# Bioreactor_Motor_PCB.net
KiCad netlist of a schematic drawn in EAGLE
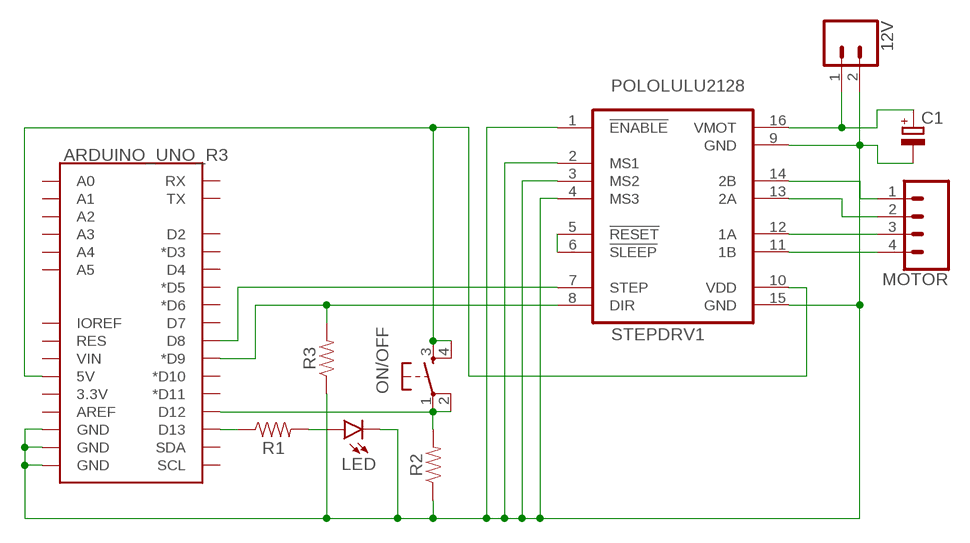
[diagram p0: schematic, sheet 1]

(export (version "E")
  (design (tool "Eeschema 10.0.6"))
  (components
    (comp (ref "12V")
      (value "CONN_02POLAR")
      (footprint "eagle-import:MOLEX-1X2")
      (libsource (lib "eagle-import") (part "CONN_02POLAR"))
    )
    (comp (ref "ARDUINO_UNO_R3")
      (value "ARDUINO_UNO_R3_SHIELDBASIC")
      (footprint "eagle-import:UNO_R3_SHIELD")
      (libsource (lib "eagle-import") (part "ARDUINO_UNO_R3_SHIELDBASIC"))
    )
    (comp (ref "C1")
      (value "CPOL-EUE3.5-8")
      (footprint "eagle-import:E3,5-8")
      (libsource (lib "eagle-import") (part "CPOL-EUE3.5-8"))
    )
    (comp (ref "LED")
      (value "TLLG4400")
      (footprint "eagle-import:LED3MM")
      (fields (field (name "MF") "VISHAY SEMICONDUCTOR"))
      (libsource (lib "eagle-import") (part "TLLG4400"))
    )
    (comp (ref "MOTOR")
      (value "CONN_04POLAR")
      (footprint "eagle-import:MOLEX-1X4")
      (libsource (lib "eagle-import") (part "CONN_04POLAR"))
    )
    (comp (ref "ON/OFF")
      (value "TAC_SWITCHPTH")
      (footprint "eagle-import:TACTILE-PTH")
      (libsource (lib "eagle-import") (part "TAC_SWITCHPTH"))
    )
    (comp (ref "R1")
      (value "1M")
      (footprint "eagle-import:AXIAL-0.3")
      (libsource (lib "eagle-import") (part "1MOHM-HORIZ-1/4W-5%"))
    )
    (comp (ref "R2")
      (value "1k")
      (footprint "eagle-import:AXIAL-0.3")
      (libsource (lib "eagle-import") (part "1KOHM-HORIZ-1/4W-1%"))
    )
    (comp (ref "R3")
      (value "1k")
      (footprint "eagle-import:AXIAL-0.3")
      (libsource (lib "eagle-import") (part "1KOHM-HORIZ-1/4W-1%"))
    )
    (comp (ref "STEPDRV1")
      (value "POLOLULU2128")
      (footprint "eagle-import:POLOLULU2128")
      (libsource (lib "eagle-import") (part "POLOLULU2128"))
    )
  )
  (nets
    (net (code "1") (name "Net-(ARDUINO_UNO_R3-*D9)") (class "Default")
      (node (ref "ARDUINO_UNO_R3") (pin "D9") (pinfunction "*D9_D9") (pintype "bidirectional"))
      (node (ref "R3") (pin "P$2") (pinfunction "2_P$2") (pintype "passive"))
      (node (ref "STEPDRV1") (pin "8") (pinfunction "DIR_8") (pintype "input"))
    )
    (net (code "2") (name "Net-(LED-C)") (class "Default")
      (node (ref "12V") (pin "2") (pinfunction "2_2") (pintype "passive"))
      (node (ref "ARDUINO_UNO_R3") (pin "GND@0") (pinfunction "GND_GND@0") (pintype "bidirectional"))
      (node (ref "ARDUINO_UNO_R3") (pin "GND@1") (pinfunction "GND_GND@1") (pintype "bidirectional"))
      (node (ref "ARDUINO_UNO_R3") (pin "GND@2") (pinfunction "GND_GND@2") (pintype "bidirectional"))
      (node (ref "C1") (pin "-") (pinfunction "-_-") (pintype "passive"))
      (node (ref "LED") (pin "K") (pinfunction "C_K") (pintype "passive"))
      (node (ref "R2") (pin "P$1") (pinfunction "1_P$1") (pintype "passive"))
      (node (ref "R3") (pin "P$1") (pinfunction "1_P$1") (pintype "passive"))
      (node (ref "STEPDRV1") (pin "1") (pinfunction "~{ENABLE}_1") (pintype "input"))
      (node (ref "STEPDRV1") (pin "15") (pinfunction "GND_15") (pintype "power_in"))
      (node (ref "STEPDRV1") (pin "2") (pinfunction "MS1_2") (pintype "input"))
      (node (ref "STEPDRV1") (pin "3") (pinfunction "MS2_3") (pintype "input"))
      (node (ref "STEPDRV1") (pin "4") (pinfunction "MS3_4") (pintype "input"))
      (node (ref "STEPDRV1") (pin "9") (pinfunction "GND_9") (pintype "power_in"))
    )
    (net (code "3") (name "Net-(R1-1)") (class "Default")
      (node (ref "ARDUINO_UNO_R3") (pin "D13") (pinfunction "D13_D13") (pintype "bidirectional"))
      (node (ref "R1") (pin "P$1") (pinfunction "1_P$1") (pintype "passive"))
    )
    (net (code "4") (name "Net-(R1-2)") (class "Default")
      (node (ref "LED") (pin "A") (pinfunction "A_A") (pintype "passive"))
      (node (ref "R1") (pin "P$2") (pinfunction "2_P$2") (pintype "passive"))
    )
    (net (code "5") (name "Net-(R2-2)") (class "Default")
      (node (ref "ARDUINO_UNO_R3") (pin "D12") (pinfunction "D12_D12") (pintype "bidirectional"))
      (node (ref "ON/OFF") (pin "1") (pinfunction "1_1") (pintype "passive"))
      (node (ref "ON/OFF") (pin "2") (pinfunction "2_2") (pintype "passive"))
      (node (ref "R2") (pin "P$2") (pinfunction "2_P$2") (pintype "passive"))
    )
    (net (code "6") (name "Net-(STEPDRV1-1A)") (class "Default")
      (node (ref "MOTOR") (pin "3") (pinfunction "3_3") (pintype "passive"))
      (node (ref "STEPDRV1") (pin "12") (pinfunction "1A_12") (pintype "output"))
    )
    (net (code "7") (name "Net-(STEPDRV1-1B)") (class "Default")
      (node (ref "MOTOR") (pin "4") (pinfunction "4_4") (pintype "passive"))
      (node (ref "STEPDRV1") (pin "11") (pinfunction "1B_11") (pintype "output"))
    )
    (net (code "8") (name "Net-(STEPDRV1-2A)") (class "Default")
      (node (ref "MOTOR") (pin "2") (pinfunction "2_2") (pintype "passive"))
      (node (ref "STEPDRV1") (pin "13") (pinfunction "2A_13") (pintype "output"))
    )
    (net (code "9") (name "Net-(STEPDRV1-2B)") (class "Default")
      (node (ref "MOTOR") (pin "1") (pinfunction "1_1") (pintype "passive"))
      (node (ref "STEPDRV1") (pin "14") (pinfunction "2B_14") (pintype "output"))
    )
    (net (code "10") (name "Net-(STEPDRV1-STEP)") (class "Default")
      (node (ref "ARDUINO_UNO_R3") (pin "D8") (pinfunction "D8_D8") (pintype "bidirectional"))
      (node (ref "STEPDRV1") (pin "7") (pinfunction "STEP_7") (pintype "input"))
    )
    (net (code "11") (name "Net-(STEPDRV1-VDD)") (class "Default")
      (node (ref "ARDUINO_UNO_R3") (pin "5V") (pinfunction "5V_5V") (pintype "bidirectional"))
      (node (ref "ON/OFF") (pin "3") (pinfunction "3_3") (pintype "passive"))
      (node (ref "ON/OFF") (pin "4") (pinfunction "4_4") (pintype "passive"))
      (node (ref "STEPDRV1") (pin "10") (pinfunction "VDD_10") (pintype "power_in"))
    )
    (net (code "12") (name "Net-(STEPDRV1-VMOT)") (class "Default")
      (node (ref "12V") (pin "1") (pinfunction "1_1") (pintype "passive"))
      (node (ref "C1") (pin "+") (pinfunction "+_+") (pintype "passive"))
      (node (ref "STEPDRV1") (pin "16") (pinfunction "VMOT_16") (pintype "power_in"))
    )
    (net (code "13") (name "Net-(STEPDRV1-~{RESET})") (class "Default")
      (node (ref "STEPDRV1") (pin "5") (pinfunction "~{RESET}_5") (pintype "input"))
      (node (ref "STEPDRV1") (pin "6") (pinfunction "~{SLEEP}_6") (pintype "input"))
    )
    (net (code "14") (name "unconnected-(ARDUINO_UNO_R3-*D3-PadD3)") (class "Default")
      (node (ref "ARDUINO_UNO_R3") (pin "D3") (pinfunction "*D3_D3") (pintype "bidirectional"))
    )
    (net (code "15") (name "unconnected-(ARDUINO_UNO_R3-*D5-PadD5)") (class "Default")
      (node (ref "ARDUINO_UNO_R3") (pin "D5") (pinfunction "*D5_D5") (pintype "bidirectional"))
    )
    (net (code "16") (name "unconnected-(ARDUINO_UNO_R3-*D6-PadD6)") (class "Default")
      (node (ref "ARDUINO_UNO_R3") (pin "D6") (pinfunction "*D6_D6") (pintype "bidirectional"))
    )
    (net (code "17") (name "unconnected-(ARDUINO_UNO_R3-*D10-PadD10)") (class "Default")
      (node (ref "ARDUINO_UNO_R3") (pin "D10") (pinfunction "*D10_D10") (pintype "bidirectional"))
    )
    (net (code "18") (name "unconnected-(ARDUINO_UNO_R3-*D11-PadD11)") (class "Default")
      (node (ref "ARDUINO_UNO_R3") (pin "D11") (pinfunction "*D11_D11") (pintype "bidirectional"))
    )
    (net (code "19") (name "unconnected-(ARDUINO_UNO_R3-Pad3.3V)") (class "Default")
      (node (ref "ARDUINO_UNO_R3") (pin "3.3V") (pinfunction "3.3V_3.3V") (pintype "bidirectional"))
    )
    (net (code "20") (name "unconnected-(ARDUINO_UNO_R3-PadA0)") (class "Default")
      (node (ref "ARDUINO_UNO_R3") (pin "A0") (pinfunction "A0_A0") (pintype "bidirectional"))
    )
    (net (code "21") (name "unconnected-(ARDUINO_UNO_R3-PadA1)") (class "Default")
      (node (ref "ARDUINO_UNO_R3") (pin "A1") (pinfunction "A1_A1") (pintype "bidirectional"))
    )
    (net (code "22") (name "unconnected-(ARDUINO_UNO_R3-PadA2)") (class "Default")
      (node (ref "ARDUINO_UNO_R3") (pin "A2") (pinfunction "A2_A2") (pintype "bidirectional"))
    )
    (net (code "23") (name "unconnected-(ARDUINO_UNO_R3-PadA3)") (class "Default")
      (node (ref "ARDUINO_UNO_R3") (pin "A3") (pinfunction "A3_A3") (pintype "bidirectional"))
    )
    (net (code "24") (name "unconnected-(ARDUINO_UNO_R3-PadA4)") (class "Default")
      (node (ref "ARDUINO_UNO_R3") (pin "A4") (pinfunction "A4_A4") (pintype "bidirectional"))
    )
    (net (code "25") (name "unconnected-(ARDUINO_UNO_R3-PadA5)") (class "Default")
      (node (ref "ARDUINO_UNO_R3") (pin "A5") (pinfunction "A5_A5") (pintype "bidirectional"))
    )
    (net (code "26") (name "unconnected-(ARDUINO_UNO_R3-PadAREF)") (class "Default")
      (node (ref "ARDUINO_UNO_R3") (pin "AREF") (pinfunction "AREF_AREF") (pintype "bidirectional"))
    )
    (net (code "27") (name "unconnected-(ARDUINO_UNO_R3-PadD2)") (class "Default")
      (node (ref "ARDUINO_UNO_R3") (pin "D2") (pinfunction "D2_D2") (pintype "bidirectional"))
    )
    (net (code "28") (name "unconnected-(ARDUINO_UNO_R3-PadD4)") (class "Default")
      (node (ref "ARDUINO_UNO_R3") (pin "D4") (pinfunction "D4_D4") (pintype "bidirectional"))
    )
    (net (code "29") (name "unconnected-(ARDUINO_UNO_R3-PadD7)") (class "Default")
      (node (ref "ARDUINO_UNO_R3") (pin "D7") (pinfunction "D7_D7") (pintype "bidirectional"))
    )
    (net (code "30") (name "unconnected-(ARDUINO_UNO_R3-PadIOREF)") (class "Default")
      (node (ref "ARDUINO_UNO_R3") (pin "IOREF") (pinfunction "IOREF_IOREF") (pintype "bidirectional"))
    )
    (net (code "31") (name "unconnected-(ARDUINO_UNO_R3-PadRES)") (class "Default")
      (node (ref "ARDUINO_UNO_R3") (pin "RES") (pinfunction "RES_RES") (pintype "bidirectional"))
    )
    (net (code "32") (name "unconnected-(ARDUINO_UNO_R3-PadRX)") (class "Default")
      (node (ref "ARDUINO_UNO_R3") (pin "RX") (pinfunction "RX_RX") (pintype "bidirectional"))
    )
    (net (code "33") (name "unconnected-(ARDUINO_UNO_R3-PadSCL)") (class "Default")
      (node (ref "ARDUINO_UNO_R3") (pin "SCL") (pinfunction "SCL_SCL") (pintype "bidirectional"))
    )
    (net (code "34") (name "unconnected-(ARDUINO_UNO_R3-PadSDA)") (class "Default")
      (node (ref "ARDUINO_UNO_R3") (pin "SDA") (pinfunction "SDA_SDA") (pintype "bidirectional"))
    )
    (net (code "35") (name "unconnected-(ARDUINO_UNO_R3-PadTX)") (class "Default")
      (node (ref "ARDUINO_UNO_R3") (pin "TX") (pinfunction "TX_TX") (pintype "bidirectional"))
    )
    (net (code "36") (name "unconnected-(ARDUINO_UNO_R3-PadVIN)") (class "Default")
      (node (ref "ARDUINO_UNO_R3") (pin "VIN") (pinfunction "VIN_VIN") (pintype "bidirectional"))
    )
  )
)
